# node1.net
KiCad netlist of a schematic drawn in Altium Designer
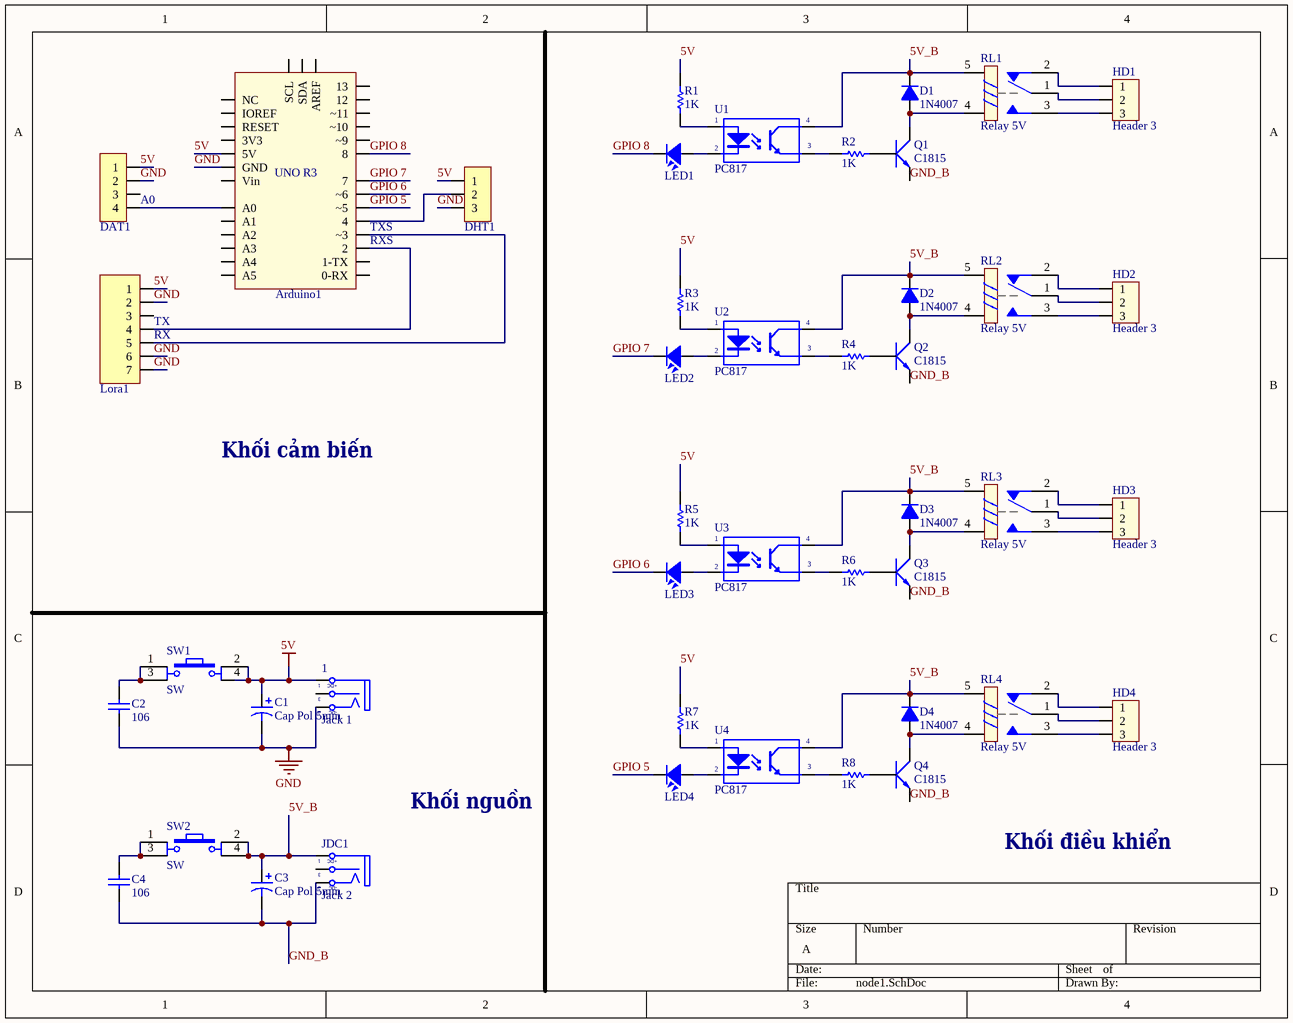
[diagram p0: node1.SchDoc]

(export (version "E")
  (design (tool "Eeschema 10.0.6"))
  (components
    (comp (ref "1")
      (value "Jack 1")
      (footprint "DC-IN")
      (description "Cắm")
      (libsource (lib "THU VIEN SCH") (part "Jac_DC"))
    )
    (comp (ref "Arduino1")
      (value "Arduino Uno R3")
      (footprint "Arduino UNO R3")
      (description "Arduino UNO R3")
      (libsource (lib "LIBRARY1") (part "Arduino Uno R3"))
    )
    (comp (ref "C1")
      (value "Cap Pol 5mm")
      (footprint "C5mm")
      (description "Polarized Capacitor (Axial)")
      (fields (field (name "PUBLISHER") "Altium Limited"))
      (libsource (lib "My Library") (part "Cap Pol 5mm"))
    )
    (comp (ref "C2")
      (value "106")
      (footprint "Tu 0805")
      (description "Dán")
      (libsource (lib "THU VIEN SCH") (part "Tu 0805 106 16V 10%"))
    )
    (comp (ref "C3")
      (value "Cap Pol 5mm")
      (footprint "C5mm")
      (description "Polarized Capacitor (Axial)")
      (fields (field (name "PUBLISHER") "Altium Limited"))
      (libsource (lib "My Library") (part "Cap Pol 5mm"))
    )
    (comp (ref "C4")
      (value "106")
      (footprint "Tu 0805")
      (description "Dán")
      (libsource (lib "THU VIEN SCH") (part "Tu 0805 106 16V 10%"))
    )
    (comp (ref "D1")
      (value "1N4007")
      (footprint "D1A")
      (description "Diode 1A")
      (libsource (lib "syhaunguyen") (part "D1A"))
    )
    (comp (ref "D2")
      (value "1N4007")
      (footprint "D1A")
      (description "Diode 1A")
      (libsource (lib "syhaunguyen") (part "D1A"))
    )
    (comp (ref "D3")
      (value "1N4007")
      (footprint "D1A")
      (description "Diode 1A")
      (libsource (lib "syhaunguyen") (part "D1A"))
    )
    (comp (ref "D4")
      (value "1N4007")
      (footprint "D1A")
      (description "Diode 1A")
      (libsource (lib "syhaunguyen") (part "D1A"))
    )
    (comp (ref "DAT1")
      (value "~")
      (footprint "JP4-C1T")
      (description "WR-PHD 2.54 mm Angled Socket Header")
      (fields
        (field (name "MANUFACTURER") "Würth Elektronik eiSos GmbH")
        (field (name "PARTNO") "613004143121")
        (field (name "CREATED BY") "Karrer Zheng")
      )
      (libsource (lib "LIBRARY1") (part "JP4"))
    )
    (comp (ref "DHT1")
      (value "~")
      (footprint "JP3-C1T")
      (description "WR-PHD 2.54 mm Angled Socket Header")
      (fields
        (field (name "MANUFACTURER") "Würth Elektronik eiSos GmbH")
        (field (name "PARTNO") "613003143121")
        (field (name "CREATED BY") "Karrer Zheng")
      )
      (libsource (lib "LIBRARY1") (part "JP3"))
    )
    (comp (ref "HD1")
      (value "Header 3")
      (footprint "HED3")
      (description "Header 3 (Green)")
      (libsource (lib "syhaunguyen") (part "Hed3"))
    )
    (comp (ref "HD2")
      (value "Header 3")
      (footprint "HED3")
      (description "Header 3 (Green)")
      (libsource (lib "syhaunguyen") (part "Hed3"))
    )
    (comp (ref "HD3")
      (value "Header 3")
      (footprint "HED3")
      (description "Header 3 (Green)")
      (libsource (lib "syhaunguyen") (part "Hed3"))
    )
    (comp (ref "HD4")
      (value "Header 3")
      (footprint "HED3")
      (description "Header 3 (Green)")
      (libsource (lib "syhaunguyen") (part "Hed3"))
    )
    (comp (ref "JDC1")
      (value "Jack 2")
      (footprint "DC-IN")
      (description "Cắm")
      (libsource (lib "THU VIEN SCH") (part "Jac_DC"))
    )
    (comp (ref "LED1")
      (value "LED")
      (footprint "LED-3")
      (description "LED Single colour Green and Red")
      (libsource (lib "syhaunguyen") (part "LED"))
    )
    (comp (ref "LED2")
      (value "LED")
      (footprint "LED-3")
      (description "LED Single colour Green and Red")
      (libsource (lib "syhaunguyen") (part "LED"))
    )
    (comp (ref "LED3")
      (value "LED")
      (footprint "LED-3")
      (description "LED Single colour Green and Red")
      (libsource (lib "syhaunguyen") (part "LED"))
    )
    (comp (ref "LED4")
      (value "LED")
      (footprint "LED-3")
      (description "LED Single colour Green and Red")
      (libsource (lib "syhaunguyen") (part "LED"))
    )
    (comp (ref "Lora1")
      (value "~")
      (footprint "JP7-C1T")
      (description "WR-PHD 2.54 mm Angled Socket Header")
      (fields
        (field (name "MANUFACTURER") "Würth Elektronik eiSos GmbH")
        (field (name "PARTNO") "613007143121")
        (field (name "CREATED BY") "Karrer Zheng")
      )
      (libsource (lib "LIBRARY1") (part "JP7"))
    )
    (comp (ref "Q1")
      (value "C1815")
      (footprint "QTO-92")
      (description "NPN 600mW, ECB")
      (libsource (lib "syhaunguyen") (part "C1815"))
    )
    (comp (ref "Q2")
      (value "C1815")
      (footprint "QTO-92")
      (description "NPN 600mW, ECB")
      (libsource (lib "syhaunguyen") (part "C1815"))
    )
    (comp (ref "Q3")
      (value "C1815")
      (footprint "QTO-92")
      (description "NPN 600mW, ECB")
      (libsource (lib "syhaunguyen") (part "C1815"))
    )
    (comp (ref "Q4")
      (value "C1815")
      (footprint "QTO-92")
      (description "NPN 600mW, ECB")
      (libsource (lib "syhaunguyen") (part "C1815"))
    )
    (comp (ref "R1")
      (value "1K")
      (footprint "R1/4W")
      (description "Resistor")
      (fields
        (field (name "MANUFACTURER") "Generic Components")
        (field (name "Comment") "Res1")
        (field (name "PUBLISHER") "Altium Hobart Technology Centre")
      )
      (libsource (lib "syhaunguyen") (part "Res1_1"))
    )
    (comp (ref "R2")
      (value "1K")
      (footprint "R1/4W")
      (description "Resistor")
      (fields
        (field (name "MANUFACTURER") "Generic Components")
        (field (name "Comment") "Res1")
        (field (name "PUBLISHER") "Altium Hobart Technology Centre")
      )
      (libsource (lib "syhaunguyen") (part "Res1_1"))
    )
    (comp (ref "R3")
      (value "1K")
      (footprint "R1/4W")
      (description "Resistor")
      (fields
        (field (name "MANUFACTURER") "Generic Components")
        (field (name "Comment") "Res1")
        (field (name "PUBLISHER") "Altium Hobart Technology Centre")
      )
      (libsource (lib "syhaunguyen") (part "Res1_1"))
    )
    (comp (ref "R4")
      (value "1K")
      (footprint "R1/4W")
      (description "Resistor")
      (fields
        (field (name "MANUFACTURER") "Generic Components")
        (field (name "Comment") "Res1")
        (field (name "PUBLISHER") "Altium Hobart Technology Centre")
      )
      (libsource (lib "syhaunguyen") (part "Res1_1"))
    )
    (comp (ref "R5")
      (value "1K")
      (footprint "R1/4W")
      (description "Resistor")
      (fields
        (field (name "MANUFACTURER") "Generic Components")
        (field (name "Comment") "Res1")
        (field (name "PUBLISHER") "Altium Hobart Technology Centre")
      )
      (libsource (lib "syhaunguyen") (part "Res1_1"))
    )
    (comp (ref "R6")
      (value "1K")
      (footprint "R1/4W")
      (description "Resistor")
      (fields
        (field (name "MANUFACTURER") "Generic Components")
        (field (name "Comment") "Res1")
        (field (name "PUBLISHER") "Altium Hobart Technology Centre")
      )
      (libsource (lib "syhaunguyen") (part "Res1_1"))
    )
    (comp (ref "R7")
      (value "1K")
      (footprint "R1/4W")
      (description "Resistor")
      (fields
        (field (name "MANUFACTURER") "Generic Components")
        (field (name "Comment") "Res1")
        (field (name "PUBLISHER") "Altium Hobart Technology Centre")
      )
      (libsource (lib "syhaunguyen") (part "Res1_1"))
    )
    (comp (ref "R8")
      (value "1K")
      (footprint "R1/4W")
      (description "Resistor")
      (fields
        (field (name "MANUFACTURER") "Generic Components")
        (field (name "Comment") "Res1")
        (field (name "PUBLISHER") "Altium Hobart Technology Centre")
      )
      (libsource (lib "syhaunguyen") (part "Res1_1"))
    )
    (comp (ref "RL1")
      (value "Relay 5V")
      (footprint "RL_SPDT_10A")
      (description "Relay SPDT,10A - 12VDC 5 Pin")
      (libsource (lib "syhaunguyen") (part "Relay 1"))
    )
    (comp (ref "RL2")
      (value "Relay 5V")
      (footprint "RL_SPDT_10A")
      (description "Relay SPDT,10A - 12VDC 5 Pin")
      (libsource (lib "syhaunguyen") (part "Relay 1"))
    )
    (comp (ref "RL3")
      (value "Relay 5V")
      (footprint "RL_SPDT_10A")
      (description "Relay SPDT,10A - 12VDC 5 Pin")
      (libsource (lib "syhaunguyen") (part "Relay 1"))
    )
    (comp (ref "RL4")
      (value "Relay 5V")
      (footprint "RL_SPDT_10A")
      (description "Relay SPDT,10A - 12VDC 5 Pin")
      (libsource (lib "syhaunguyen") (part "Relay 1"))
    )
    (comp (ref "SW1")
      (value "SW")
      (footprint "SW4")
      (description "Switch button 4 pin")
      (libsource (lib "My Library") (part "SW4"))
    )
    (comp (ref "SW2")
      (value "SW")
      (footprint "SW4")
      (description "Switch button 4 pin")
      (libsource (lib "My Library") (part "SW4"))
    )
    (comp (ref "U1")
      (value "PC817")
      (footprint "DIP4/W0.3")
      (description "Single Opto")
      (libsource (lib "syhaunguyen") (part "PC817"))
    )
    (comp (ref "U2")
      (value "PC817")
      (footprint "DIP4/W0.3")
      (description "Single Opto")
      (libsource (lib "syhaunguyen") (part "PC817"))
    )
    (comp (ref "U3")
      (value "PC817")
      (footprint "DIP4/W0.3")
      (description "Single Opto")
      (libsource (lib "syhaunguyen") (part "PC817"))
    )
    (comp (ref "U4")
      (value "PC817")
      (footprint "DIP4/W0.3")
      (description "Single Opto")
      (libsource (lib "syhaunguyen") (part "PC817"))
    )
  )
  (nets
    (net (code "1") (name "/5V_B") (class "Default")
      (node (ref "C3") (pin "1") (pinfunction "1_1") (pintype "passive"))
      (node (ref "D1") (pin "2") (pinfunction "K_2") (pintype "passive"))
      (node (ref "D2") (pin "2") (pinfunction "K_2") (pintype "passive"))
      (node (ref "D3") (pin "2") (pinfunction "K_2") (pintype "passive"))
      (node (ref "D4") (pin "2") (pinfunction "K_2") (pintype "passive"))
      (node (ref "JDC1") (pin "1") (pinfunction "T_1") (pintype "passive"))
      (node (ref "RL1") (pin "5") (pinfunction "5_5") (pintype "passive"))
      (node (ref "RL2") (pin "5") (pinfunction "5_5") (pintype "passive"))
      (node (ref "RL3") (pin "5") (pinfunction "5_5") (pintype "passive"))
      (node (ref "RL4") (pin "5") (pinfunction "5_5") (pintype "passive"))
      (node (ref "SW2") (pin "2") (pintype "passive"))
      (node (ref "SW2") (pin "4") (pintype "passive"))
      (node (ref "U1") (pin "4") (pinfunction "C_4") (pintype "passive"))
      (node (ref "U2") (pin "4") (pinfunction "C_4") (pintype "passive"))
      (node (ref "U3") (pin "4") (pinfunction "C_4") (pintype "passive"))
      (node (ref "U4") (pin "4") (pinfunction "C_4") (pintype "passive"))
    )
    (net (code "2") (name "/GND_B") (class "Default")
      (node (ref "C3") (pin "2") (pinfunction "2_2") (pintype "passive"))
      (node (ref "C4") (pin "2") (pinfunction "2_2") (pintype "passive"))
      (node (ref "JDC1") (pin "2") (pinfunction "TN_2") (pintype "passive"))
      (node (ref "Q1") (pin "1") (pinfunction "E_1") (pintype "passive"))
      (node (ref "Q2") (pin "1") (pinfunction "E_1") (pintype "passive"))
      (node (ref "Q3") (pin "1") (pinfunction "E_1") (pintype "passive"))
      (node (ref "Q4") (pin "1") (pinfunction "E_1") (pintype "passive"))
    )
    (net (code "3") (name "/GPIO 5") (class "Default")
      (node (ref "Arduino1") (pin "~5") (pinfunction "~5_~5") (pintype "passive"))
      (node (ref "LED4") (pin "2") (pinfunction "2_2") (pintype "passive"))
    )
    (net (code "4") (name "/GPIO 6") (class "Default")
      (node (ref "Arduino1") (pin "~6") (pinfunction "~6_~6") (pintype "passive"))
      (node (ref "LED3") (pin "2") (pinfunction "2_2") (pintype "passive"))
    )
    (net (code "5") (name "/GPIO 7") (class "Default")
      (node (ref "Arduino1") (pin "7") (pinfunction "7_7") (pintype "passive"))
      (node (ref "LED2") (pin "2") (pinfunction "2_2") (pintype "passive"))
    )
    (net (code "6") (name "/GPIO 8") (class "Default")
      (node (ref "Arduino1") (pin "8") (pinfunction "8_8") (pintype "passive"))
      (node (ref "LED1") (pin "2") (pinfunction "2_2") (pintype "passive"))
    )
    (net (code "7") (name "5V") (class "Default")
      (node (ref "1") (pin "1") (pinfunction "T_1") (pintype "passive"))
      (node (ref "Arduino1") (pin "5V") (pinfunction "5V_5V") (pintype "passive"))
      (node (ref "C1") (pin "1") (pinfunction "1_1") (pintype "passive"))
      (node (ref "DAT1") (pin "1") (pinfunction "1_1") (pintype "passive"))
      (node (ref "DHT1") (pin "1") (pinfunction "1_1") (pintype "passive"))
      (node (ref "Lora1") (pin "1") (pinfunction "1_1") (pintype "passive"))
      (node (ref "R1") (pin "2") (pinfunction "2_2") (pintype "passive"))
      (node (ref "R3") (pin "2") (pinfunction "2_2") (pintype "passive"))
      (node (ref "R5") (pin "2") (pinfunction "2_2") (pintype "passive"))
      (node (ref "R7") (pin "2") (pinfunction "2_2") (pintype "passive"))
      (node (ref "SW1") (pin "2") (pintype "passive"))
      (node (ref "SW1") (pin "4") (pintype "passive"))
    )
    (net (code "8") (name "GND") (class "Default")
      (node (ref "1") (pin "2") (pinfunction "TN_2") (pintype "passive"))
      (node (ref "Arduino1") (pin "GND") (pinfunction "GND_GND") (pintype "passive"))
      (node (ref "C1") (pin "2") (pinfunction "2_2") (pintype "passive"))
      (node (ref "C2") (pin "2") (pinfunction "2_2") (pintype "passive"))
      (node (ref "DAT1") (pin "2") (pinfunction "2_2") (pintype "passive"))
      (node (ref "DHT1") (pin "3") (pinfunction "3_3") (pintype "passive"))
      (node (ref "Lora1") (pin "2") (pinfunction "2_2") (pintype "passive"))
      (node (ref "Lora1") (pin "6") (pinfunction "6_6") (pintype "passive"))
      (node (ref "Lora1") (pin "7") (pinfunction "7_7") (pintype "passive"))
    )
    (net (code "9") (name "Net-(Arduino1-Pad2)") (class "Default")
      (node (ref "Arduino1") (pin "2") (pinfunction "2_2") (pintype "passive"))
      (node (ref "Lora1") (pin "4") (pinfunction "4_4") (pintype "passive"))
    )
    (net (code "10") (name "Net-(Arduino1-Pad4)") (class "Default")
      (node (ref "Arduino1") (pin "4") (pinfunction "4_4") (pintype "passive"))
      (node (ref "DHT1") (pin "2") (pinfunction "2_2") (pintype "passive"))
    )
    (net (code "11") (name "Net-(Arduino1-PadA0)") (class "Default")
      (node (ref "Arduino1") (pin "A0") (pinfunction "A0_A0") (pintype "passive"))
      (node (ref "DAT1") (pin "4") (pinfunction "4_4") (pintype "passive"))
    )
    (net (code "12") (name "Net-(Arduino1-Pad~3)") (class "Default")
      (node (ref "Arduino1") (pin "~3") (pinfunction "~3_~3") (pintype "passive"))
      (node (ref "Lora1") (pin "5") (pinfunction "5_5") (pintype "passive"))
    )
    (net (code "13") (name "Net-(C2-Pad1)") (class "Default")
      (node (ref "C2") (pin "1") (pinfunction "1_1") (pintype "passive"))
      (node (ref "SW1") (pin "1") (pintype "passive"))
      (node (ref "SW1") (pin "3") (pintype "passive"))
    )
    (net (code "14") (name "Net-(C4-Pad1)") (class "Default")
      (node (ref "C4") (pin "1") (pinfunction "1_1") (pintype "passive"))
      (node (ref "SW2") (pin "1") (pintype "passive"))
      (node (ref "SW2") (pin "3") (pintype "passive"))
    )
    (net (code "15") (name "Net-(D1-A)") (class "Default")
      (node (ref "D1") (pin "1") (pinfunction "A_1") (pintype "passive"))
      (node (ref "Q1") (pin "2") (pinfunction "C_2") (pintype "passive"))
      (node (ref "RL1") (pin "4") (pinfunction "4_4") (pintype "passive"))
    )
    (net (code "16") (name "Net-(D2-A)") (class "Default")
      (node (ref "D2") (pin "1") (pinfunction "A_1") (pintype "passive"))
      (node (ref "Q2") (pin "2") (pinfunction "C_2") (pintype "passive"))
      (node (ref "RL2") (pin "4") (pinfunction "4_4") (pintype "passive"))
    )
    (net (code "17") (name "Net-(D3-A)") (class "Default")
      (node (ref "D3") (pin "1") (pinfunction "A_1") (pintype "passive"))
      (node (ref "Q3") (pin "2") (pinfunction "C_2") (pintype "passive"))
      (node (ref "RL3") (pin "4") (pinfunction "4_4") (pintype "passive"))
    )
    (net (code "18") (name "Net-(D4-A)") (class "Default")
      (node (ref "D4") (pin "1") (pinfunction "A_1") (pintype "passive"))
      (node (ref "Q4") (pin "2") (pinfunction "C_2") (pintype "passive"))
      (node (ref "RL4") (pin "4") (pinfunction "4_4") (pintype "passive"))
    )
    (net (code "19") (name "Net-(HD1-Pad1)") (class "Default")
      (node (ref "HD1") (pin "1") (pinfunction "1_1") (pintype "passive"))
      (node (ref "RL1") (pin "2") (pinfunction "2_2") (pintype "passive"))
    )
    (net (code "20") (name "Net-(HD1-Pad2)") (class "Default")
      (node (ref "HD1") (pin "2") (pinfunction "2_2") (pintype "passive"))
      (node (ref "RL1") (pin "1") (pinfunction "1_1") (pintype "passive"))
    )
    (net (code "21") (name "Net-(HD1-Pad3)") (class "Default")
      (node (ref "HD1") (pin "3") (pinfunction "3_3") (pintype "passive"))
      (node (ref "RL1") (pin "3") (pinfunction "3_3") (pintype "passive"))
    )
    (net (code "22") (name "Net-(HD2-Pad1)") (class "Default")
      (node (ref "HD2") (pin "1") (pinfunction "1_1") (pintype "passive"))
      (node (ref "RL2") (pin "2") (pinfunction "2_2") (pintype "passive"))
    )
    (net (code "23") (name "Net-(HD2-Pad2)") (class "Default")
      (node (ref "HD2") (pin "2") (pinfunction "2_2") (pintype "passive"))
      (node (ref "RL2") (pin "1") (pinfunction "1_1") (pintype "passive"))
    )
    (net (code "24") (name "Net-(HD2-Pad3)") (class "Default")
      (node (ref "HD2") (pin "3") (pinfunction "3_3") (pintype "passive"))
      (node (ref "RL2") (pin "3") (pinfunction "3_3") (pintype "passive"))
    )
    (net (code "25") (name "Net-(HD3-Pad1)") (class "Default")
      (node (ref "HD3") (pin "1") (pinfunction "1_1") (pintype "passive"))
      (node (ref "RL3") (pin "2") (pinfunction "2_2") (pintype "passive"))
    )
    (net (code "26") (name "Net-(HD3-Pad2)") (class "Default")
      (node (ref "HD3") (pin "2") (pinfunction "2_2") (pintype "passive"))
      (node (ref "RL3") (pin "1") (pinfunction "1_1") (pintype "passive"))
    )
    (net (code "27") (name "Net-(HD3-Pad3)") (class "Default")
      (node (ref "HD3") (pin "3") (pinfunction "3_3") (pintype "passive"))
      (node (ref "RL3") (pin "3") (pinfunction "3_3") (pintype "passive"))
    )
    (net (code "28") (name "Net-(HD4-Pad1)") (class "Default")
      (node (ref "HD4") (pin "1") (pinfunction "1_1") (pintype "passive"))
      (node (ref "RL4") (pin "2") (pinfunction "2_2") (pintype "passive"))
    )
    (net (code "29") (name "Net-(HD4-Pad2)") (class "Default")
      (node (ref "HD4") (pin "2") (pinfunction "2_2") (pintype "passive"))
      (node (ref "RL4") (pin "1") (pinfunction "1_1") (pintype "passive"))
    )
    (net (code "30") (name "Net-(HD4-Pad3)") (class "Default")
      (node (ref "HD4") (pin "3") (pinfunction "3_3") (pintype "passive"))
      (node (ref "RL4") (pin "3") (pinfunction "3_3") (pintype "passive"))
    )
    (net (code "31") (name "Net-(Q1-B)") (class "Default")
      (node (ref "Q1") (pin "3") (pinfunction "B_3") (pintype "passive"))
      (node (ref "R2") (pin "1") (pinfunction "1_1") (pintype "passive"))
    )
    (net (code "32") (name "Net-(Q2-B)") (class "Default")
      (node (ref "Q2") (pin "3") (pinfunction "B_3") (pintype "passive"))
      (node (ref "R4") (pin "1") (pinfunction "1_1") (pintype "passive"))
    )
    (net (code "33") (name "Net-(Q3-B)") (class "Default")
      (node (ref "Q3") (pin "3") (pinfunction "B_3") (pintype "passive"))
      (node (ref "R6") (pin "1") (pinfunction "1_1") (pintype "passive"))
    )
    (net (code "34") (name "Net-(Q4-B)") (class "Default")
      (node (ref "Q4") (pin "3") (pinfunction "B_3") (pintype "passive"))
      (node (ref "R8") (pin "1") (pinfunction "1_1") (pintype "passive"))
    )
    (net (code "35") (name "Net-(U1-A)") (class "Default")
      (node (ref "R1") (pin "1") (pinfunction "1_1") (pintype "passive"))
      (node (ref "U1") (pin "1") (pinfunction "A_1") (pintype "passive"))
    )
    (net (code "36") (name "Net-(U1-E)") (class "Default")
      (node (ref "R2") (pin "2") (pinfunction "2_2") (pintype "passive"))
      (node (ref "U1") (pin "3") (pinfunction "E_3") (pintype "passive"))
    )
    (net (code "37") (name "Net-(U1-K)") (class "Default")
      (node (ref "LED1") (pin "1") (pinfunction "1_1") (pintype "passive"))
      (node (ref "U1") (pin "2") (pinfunction "K_2") (pintype "passive"))
    )
    (net (code "38") (name "Net-(U2-A)") (class "Default")
      (node (ref "R3") (pin "1") (pinfunction "1_1") (pintype "passive"))
      (node (ref "U2") (pin "1") (pinfunction "A_1") (pintype "passive"))
    )
    (net (code "39") (name "Net-(U2-E)") (class "Default")
      (node (ref "R4") (pin "2") (pinfunction "2_2") (pintype "passive"))
      (node (ref "U2") (pin "3") (pinfunction "E_3") (pintype "passive"))
    )
    (net (code "40") (name "Net-(U2-K)") (class "Default")
      (node (ref "LED2") (pin "1") (pinfunction "1_1") (pintype "passive"))
      (node (ref "U2") (pin "2") (pinfunction "K_2") (pintype "passive"))
    )
    (net (code "41") (name "Net-(U3-A)") (class "Default")
      (node (ref "R5") (pin "1") (pinfunction "1_1") (pintype "passive"))
      (node (ref "U3") (pin "1") (pinfunction "A_1") (pintype "passive"))
    )
    (net (code "42") (name "Net-(U3-E)") (class "Default")
      (node (ref "R6") (pin "2") (pinfunction "2_2") (pintype "passive"))
      (node (ref "U3") (pin "3") (pinfunction "E_3") (pintype "passive"))
    )
    (net (code "43") (name "Net-(U3-K)") (class "Default")
      (node (ref "LED3") (pin "1") (pinfunction "1_1") (pintype "passive"))
      (node (ref "U3") (pin "2") (pinfunction "K_2") (pintype "passive"))
    )
    (net (code "44") (name "Net-(U4-A)") (class "Default")
      (node (ref "R7") (pin "1") (pinfunction "1_1") (pintype "passive"))
      (node (ref "U4") (pin "1") (pinfunction "A_1") (pintype "passive"))
    )
    (net (code "45") (name "Net-(U4-E)") (class "Default")
      (node (ref "R8") (pin "2") (pinfunction "2_2") (pintype "passive"))
      (node (ref "U4") (pin "3") (pinfunction "E_3") (pintype "passive"))
    )
    (net (code "46") (name "Net-(U4-K)") (class "Default")
      (node (ref "LED4") (pin "1") (pinfunction "1_1") (pintype "passive"))
      (node (ref "U4") (pin "2") (pinfunction "K_2") (pintype "passive"))
    )
    (net (code "47") (name "unconnected-(1-S-Pad3)") (class "Default")
      (node (ref "1") (pin "3") (pinfunction "S_3") (pintype "power_in"))
    )
    (net (code "48") (name "unconnected-(Arduino1-Pad0-RX)") (class "Default")
      (node (ref "Arduino1") (pin "0-RX") (pinfunction "0-RX_0-RX") (pintype "passive"))
    )
    (net (code "49") (name "unconnected-(Arduino1-Pad1-TX)") (class "Default")
      (node (ref "Arduino1") (pin "1-TX") (pinfunction "1-TX_1-TX") (pintype "passive"))
    )
    (net (code "50") (name "unconnected-(Arduino1-Pad3V3)") (class "Default")
      (node (ref "Arduino1") (pin "3V3") (pinfunction "3V3_3V3") (pintype "passive"))
    )
    (net (code "51") (name "unconnected-(Arduino1-Pad12)") (class "Default")
      (node (ref "Arduino1") (pin "12") (pinfunction "12_12") (pintype "passive"))
    )
    (net (code "52") (name "unconnected-(Arduino1-Pad13)") (class "Default")
      (node (ref "Arduino1") (pin "13") (pinfunction "13_13") (pintype "passive"))
    )
    (net (code "53") (name "unconnected-(Arduino1-PadA1)") (class "Default")
      (node (ref "Arduino1") (pin "A1") (pinfunction "A1_A1") (pintype "passive"))
    )
    (net (code "54") (name "unconnected-(Arduino1-PadA2)") (class "Default")
      (node (ref "Arduino1") (pin "A2") (pinfunction "A2_A2") (pintype "passive"))
    )
    (net (code "55") (name "unconnected-(Arduino1-PadA3)") (class "Default")
      (node (ref "Arduino1") (pin "A3") (pinfunction "A3_A3") (pintype "passive"))
    )
    (net (code "56") (name "unconnected-(Arduino1-PadA4)") (class "Default")
      (node (ref "Arduino1") (pin "A4") (pinfunction "A4_A4") (pintype "passive"))
    )
    (net (code "57") (name "unconnected-(Arduino1-PadA5)") (class "Default")
      (node (ref "Arduino1") (pin "A5") (pinfunction "A5_A5") (pintype "passive"))
    )
    (net (code "58") (name "unconnected-(Arduino1-PadAREF)") (class "Default")
      (node (ref "Arduino1") (pin "AREF") (pinfunction "AREF_AREF") (pintype "passive"))
    )
    (net (code "59") (name "unconnected-(Arduino1-PadIOREF)") (class "Default")
      (node (ref "Arduino1") (pin "IOREF") (pinfunction "IOREF_IOREF") (pintype "passive"))
    )
    (net (code "60") (name "unconnected-(Arduino1-PadNC)") (class "Default")
      (node (ref "Arduino1") (pin "NC") (pinfunction "NC_NC") (pintype "passive"))
    )
    (net (code "61") (name "unconnected-(Arduino1-PadRESET)") (class "Default")
      (node (ref "Arduino1") (pin "RESET") (pinfunction "RESET_RESET") (pintype "passive"))
    )
    (net (code "62") (name "unconnected-(Arduino1-PadSCL)") (class "Default")
      (node (ref "Arduino1") (pin "SCL") (pinfunction "SCL_SCL") (pintype "passive"))
    )
    (net (code "63") (name "unconnected-(Arduino1-PadSDA)") (class "Default")
      (node (ref "Arduino1") (pin "SDA") (pinfunction "SDA_SDA") (pintype "passive"))
    )
    (net (code "64") (name "unconnected-(Arduino1-PadVin)") (class "Default")
      (node (ref "Arduino1") (pin "Vin") (pinfunction "Vin_Vin") (pintype "passive"))
    )
    (net (code "65") (name "unconnected-(Arduino1-Pad~9)") (class "Default")
      (node (ref "Arduino1") (pin "~9") (pinfunction "~9_~9") (pintype "passive"))
    )
    (net (code "66") (name "unconnected-(Arduino1-Pad~10)") (class "Default")
      (node (ref "Arduino1") (pin "~10") (pinfunction "~10_~10") (pintype "passive"))
    )
    (net (code "67") (name "unconnected-(Arduino1-Pad~11)") (class "Default")
      (node (ref "Arduino1") (pin "~11") (pinfunction "~11_~11") (pintype "passive"))
    )
    (net (code "68") (name "unconnected-(DAT1-Pad3)") (class "Default")
      (node (ref "DAT1") (pin "3") (pinfunction "3_3") (pintype "passive"))
    )
    (net (code "69") (name "unconnected-(JDC1-S-Pad3)") (class "Default")
      (node (ref "JDC1") (pin "3") (pinfunction "S_3") (pintype "power_in"))
    )
    (net (code "70") (name "unconnected-(Lora1-Pad3)") (class "Default")
      (node (ref "Lora1") (pin "3") (pinfunction "3_3") (pintype "passive"))
    )
  )
)
